# 7Segment-Display-RS232.net
KiCad netlist of a schematic drawn in EAGLE
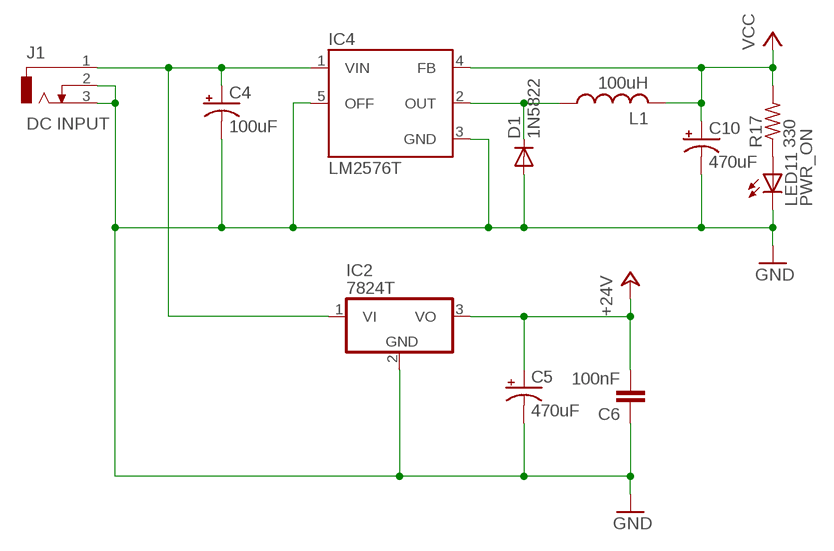
[diagram p0: schematic, sheet 1, part 1 of 2]
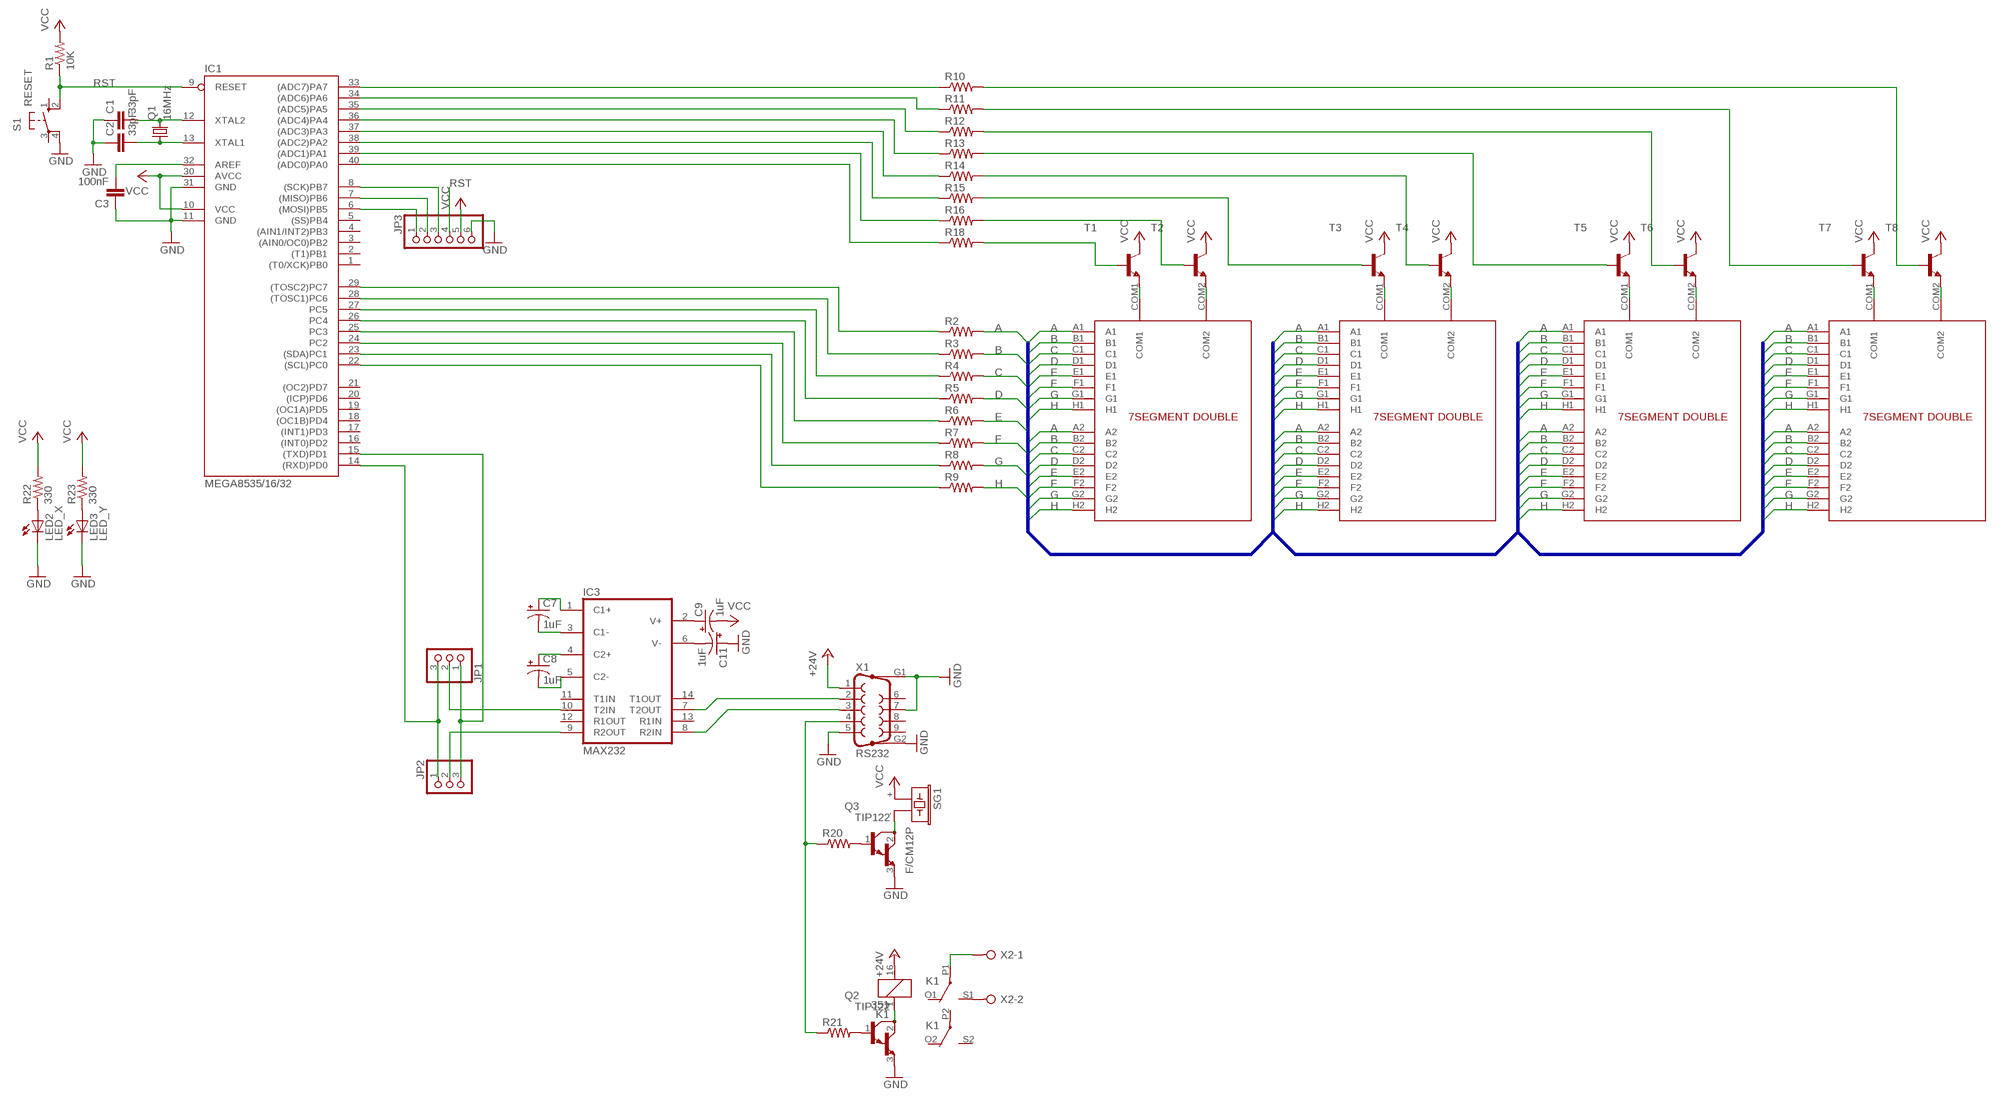
[diagram p1: schematic, sheet 1, part 2 of 2]

(export (version "E")
  (design (tool "Eeschema 10.0.6"))
  (components
    (comp (ref "C1")
      (value "33pF")
      (footprint "eagle-import:C025-024X044")
      (libsource (lib "eagle-import") (part "C-EU025-024X044"))
    )
    (comp (ref "C2")
      (value "33pF")
      (footprint "eagle-import:C025-024X044")
      (libsource (lib "eagle-import") (part "C-EU025-024X044"))
    )
    (comp (ref "C3")
      (value "100nF")
      (footprint "eagle-import:C025-024X044")
      (libsource (lib "eagle-import") (part "C-EU025-024X044"))
    )
    (comp (ref "C4")
      (value "100uF")
      (footprint "eagle-import:E2,5-6")
      (libsource (lib "eagle-import") (part "CPOL-USE2.5-6"))
    )
    (comp (ref "C5")
      (value "470uF")
      (footprint "eagle-import:E3,5-8")
      (libsource (lib "eagle-import") (part "CPOL-USE3.5-8"))
    )
    (comp (ref "C6")
      (value "100nF")
      (footprint "eagle-import:C025-024X044")
      (libsource (lib "eagle-import") (part "C-EU025-024X044"))
    )
    (comp (ref "C7")
      (value "1uF")
      (footprint "eagle-import:E2-4")
      (libsource (lib "eagle-import") (part "CPOL-USE2-4"))
    )
    (comp (ref "C8")
      (value "1uF")
      (footprint "eagle-import:E2-4")
      (libsource (lib "eagle-import") (part "CPOL-USE2-4"))
    )
    (comp (ref "C9")
      (value "1uF")
      (footprint "eagle-import:E2-4")
      (libsource (lib "eagle-import") (part "CPOL-USE2-4"))
    )
    (comp (ref "C10")
      (value "470uF")
      (footprint "eagle-import:E3,5-8")
      (libsource (lib "eagle-import") (part "CPOL-USE3.5-8"))
    )
    (comp (ref "C11")
      (value "1uF")
      (footprint "eagle-import:E2-4")
      (libsource (lib "eagle-import") (part "CPOL-USE2-4"))
    )
    (comp (ref "D1")
      (value "1N5822")
      (footprint "eagle-import:DO201-15")
      (libsource (lib "eagle-import") (part "1N5400"))
    )
    (comp (ref "IC1")
      (value "MEGA8535/16/32")
      (footprint "eagle-import:DIL40")
      (fields (field (name "MPN") "ATMEGA8535-16PU"))
      (libsource (lib "eagle-import") (part "MEGA8535-P"))
    )
    (comp (ref "IC2")
      (value "7824T")
      (footprint "eagle-import:TO220H")
      (libsource (lib "eagle-import") (part "78T24"))
    )
    (comp (ref "IC3")
      (value "MAX232")
      (footprint "eagle-import:DIL16")
      (fields (field (name "MF") "MAXIM") (field (name "MPN") "MAX232ACPE+"))
      (libsource (lib "eagle-import") (part "MAX232"))
    )
    (comp (ref "IC4")
      (value "LM2576T")
      (footprint "eagle-import:TO220-5")
      (libsource (lib "eagle-import") (part "LM2576T"))
    )
    (comp (ref "J1")
      (value "DC INPUT")
      (footprint "eagle-import:DCJ0202")
      (libsource (lib "eagle-import") (part "DCJ0202"))
    )
    (comp (ref "JP1")
      (value "PINHD-1X3")
      (footprint "eagle-import:1X03")
      (libsource (lib "eagle-import") (part "PINHD-1X3"))
    )
    (comp (ref "JP2")
      (value "PINHD-1X3")
      (footprint "eagle-import:1X03")
      (libsource (lib "eagle-import") (part "PINHD-1X3"))
    )
    (comp (ref "JP3")
      (value "PINHD-1X6")
      (footprint "eagle-import:1X06")
      (libsource (lib "eagle-import") (part "PINHD-1X6"))
    )
    (comp (ref "K1")
      (value "351")
      (footprint "eagle-import:351")
      (libsource (lib "eagle-import") (part "351"))
    )
    (comp (ref "L1")
      (value "100uH")
      (footprint "eagle-import:TJ3-U2")
      (libsource (lib "eagle-import") (part "L-USTJ3-U2"))
    )
    (comp (ref "LED2")
      (value "LED_X")
      (footprint "eagle-import:LED3MM")
      (libsource (lib "eagle-import") (part "LED3MM"))
    )
    (comp (ref "LED3")
      (value "LED_Y")
      (footprint "eagle-import:LED3MM")
      (libsource (lib "eagle-import") (part "LED3MM"))
    )
    (comp (ref "LED11")
      (value "PWR_ON")
      (footprint "eagle-import:LED3MM")
      (libsource (lib "eagle-import") (part "LED3MM"))
    )
    (comp (ref "Q1")
      (value "16MHz")
      (footprint "eagle-import:HC49_S")
      (libsource (lib "eagle-import") (part "CRYSTALHC49S"))
    )
    (comp (ref "Q2")
      (value "TIP122")
      (footprint "eagle-import:TO220")
      (libsource (lib "eagle-import") (part "TIP122"))
    )
    (comp (ref "Q3")
      (value "TIP122")
      (footprint "eagle-import:TO220")
      (libsource (lib "eagle-import") (part "TIP122"))
    )
    (comp (ref "R1")
      (value "10K")
      (footprint "eagle-import:0207_10")
      (libsource (lib "eagle-import") (part "R-US_0207/10"))
    )
    (comp (ref "R2")
      (value "R-US_0207/2V")
      (footprint "eagle-import:0207_2V")
      (libsource (lib "eagle-import") (part "R-US_0207/2V"))
    )
    (comp (ref "R3")
      (value "R-US_0207/2V")
      (footprint "eagle-import:0207_2V")
      (libsource (lib "eagle-import") (part "R-US_0207/2V"))
    )
    (comp (ref "R4")
      (value "R-US_0207/2V")
      (footprint "eagle-import:0207_2V")
      (libsource (lib "eagle-import") (part "R-US_0207/2V"))
    )
    (comp (ref "R5")
      (value "R-US_0207/2V")
      (footprint "eagle-import:0207_2V")
      (libsource (lib "eagle-import") (part "R-US_0207/2V"))
    )
    (comp (ref "R6")
      (value "R-US_0207/2V")
      (footprint "eagle-import:0207_2V")
      (libsource (lib "eagle-import") (part "R-US_0207/2V"))
    )
    (comp (ref "R7")
      (value "R-US_0207/2V")
      (footprint "eagle-import:0207_2V")
      (libsource (lib "eagle-import") (part "R-US_0207/2V"))
    )
    (comp (ref "R8")
      (value "R-US_0207/2V")
      (footprint "eagle-import:0207_2V")
      (libsource (lib "eagle-import") (part "R-US_0207/2V"))
    )
    (comp (ref "R9")
      (value "R-US_0207/2V")
      (footprint "eagle-import:0207_2V")
      (libsource (lib "eagle-import") (part "R-US_0207/2V"))
    )
    (comp (ref "R10")
      (value "R-US_0207/2V")
      (footprint "eagle-import:0207_2V")
      (libsource (lib "eagle-import") (part "R-US_0207/2V"))
    )
    (comp (ref "R11")
      (value "R-US_0207/2V")
      (footprint "eagle-import:0207_2V")
      (libsource (lib "eagle-import") (part "R-US_0207/2V"))
    )
    (comp (ref "R12")
      (value "R-US_0207/2V")
      (footprint "eagle-import:0207_2V")
      (libsource (lib "eagle-import") (part "R-US_0207/2V"))
    )
    (comp (ref "R13")
      (value "R-US_0207/2V")
      (footprint "eagle-import:0207_2V")
      (libsource (lib "eagle-import") (part "R-US_0207/2V"))
    )
    (comp (ref "R14")
      (value "R-US_0207/2V")
      (footprint "eagle-import:0207_2V")
      (libsource (lib "eagle-import") (part "R-US_0207/2V"))
    )
    (comp (ref "R15")
      (value "R-US_0207/2V")
      (footprint "eagle-import:0207_2V")
      (libsource (lib "eagle-import") (part "R-US_0207/2V"))
    )
    (comp (ref "R16")
      (value "R-US_0207/2V")
      (footprint "eagle-import:0207_2V")
      (libsource (lib "eagle-import") (part "R-US_0207/2V"))
    )
    (comp (ref "R17")
      (value "330")
      (footprint "eagle-import:0207_2V")
      (libsource (lib "eagle-import") (part "R-US_0207/2V"))
    )
    (comp (ref "R18")
      (value "R-US_0207/2V")
      (footprint "eagle-import:0207_2V")
      (libsource (lib "eagle-import") (part "R-US_0207/2V"))
    )
    (comp (ref "R20")
      (value "R-US_0207/2V")
      (footprint "eagle-import:0207_2V")
      (libsource (lib "eagle-import") (part "R-US_0207/2V"))
    )
    (comp (ref "R21")
      (value "R-US_0207/2V")
      (footprint "eagle-import:0207_2V")
      (libsource (lib "eagle-import") (part "R-US_0207/2V"))
    )
    (comp (ref "R22")
      (value "330")
      (footprint "eagle-import:0207_2V")
      (libsource (lib "eagle-import") (part "R-US_0207/2V"))
    )
    (comp (ref "R23")
      (value "330")
      (footprint "eagle-import:0207_2V")
      (libsource (lib "eagle-import") (part "R-US_0207/2V"))
    )
    (comp (ref "S1")
      (value "RESET")
      (footprint "eagle-import:B3F-10XX")
      (fields (field (name "MPN") "B3F-1000"))
      (libsource (lib "eagle-import") (part "10-XX"))
    )
    (comp (ref "SG1")
      (value "F/CM12P")
      (footprint "eagle-import:F_CM12P")
      (libsource (lib "eagle-import") (part "F/CM12P"))
    )
    (comp (ref "T1")
      (value "2N2222-NPN-TO92-EBC")
      (footprint "eagle-import:TO92-EBC")
      (libsource (lib "eagle-import") (part "-NPN-TO92-EBC2N2222"))
    )
    (comp (ref "T2")
      (value "2N2222-NPN-TO92-EBC")
      (footprint "eagle-import:TO92-EBC")
      (libsource (lib "eagle-import") (part "-NPN-TO92-EBC2N2222"))
    )
    (comp (ref "T3")
      (value "2N2222-NPN-TO92-EBC")
      (footprint "eagle-import:TO92-EBC")
      (libsource (lib "eagle-import") (part "-NPN-TO92-EBC2N2222"))
    )
    (comp (ref "T4")
      (value "2N2222-NPN-TO92-EBC")
      (footprint "eagle-import:TO92-EBC")
      (libsource (lib "eagle-import") (part "-NPN-TO92-EBC2N2222"))
    )
    (comp (ref "T5")
      (value "2N2222-NPN-TO92-EBC")
      (footprint "eagle-import:TO92-EBC")
      (libsource (lib "eagle-import") (part "-NPN-TO92-EBC2N2222"))
    )
    (comp (ref "T6")
      (value "2N2222-NPN-TO92-EBC")
      (footprint "eagle-import:TO92-EBC")
      (libsource (lib "eagle-import") (part "-NPN-TO92-EBC2N2222"))
    )
    (comp (ref "T7")
      (value "2N2222-NPN-TO92-EBC")
      (footprint "eagle-import:TO92-EBC")
      (libsource (lib "eagle-import") (part "-NPN-TO92-EBC2N2222"))
    )
    (comp (ref "T8")
      (value "2N2222-NPN-TO92-EBC")
      (footprint "eagle-import:TO92-EBC")
      (libsource (lib "eagle-import") (part "-NPN-TO92-EBC2N2222"))
    )
    (comp (ref "U$1")
      (value "7SEGMENT_DOUBLE")
      (footprint "eagle-import:7SEGMENT_DOUBLE")
      (libsource (lib "eagle-import") (part "7SEGMENT_DOUBLE"))
    )
    (comp (ref "U$2")
      (value "7SEGMENT_DOUBLE")
      (footprint "eagle-import:7SEGMENT_DOUBLE")
      (libsource (lib "eagle-import") (part "7SEGMENT_DOUBLE"))
    )
    (comp (ref "U$3")
      (value "7SEGMENT_DOUBLE")
      (footprint "eagle-import:7SEGMENT_DOUBLE")
      (libsource (lib "eagle-import") (part "7SEGMENT_DOUBLE"))
    )
    (comp (ref "U$4")
      (value "7SEGMENT_DOUBLE")
      (footprint "eagle-import:7SEGMENT_DOUBLE")
      (libsource (lib "eagle-import") (part "7SEGMENT_DOUBLE"))
    )
    (comp (ref "X1")
      (value "RS232")
      (footprint "eagle-import:F09HP")
      (libsource (lib "eagle-import") (part "F09HP"))
    )
    (comp (ref "X2")
      (value "W237-02P")
      (footprint "eagle-import:W237-132")
      (libsource (lib "eagle-import") (part "W237-02P"))
    )
  )
  (nets
    (net (code "1") (name "+24V") (class "Default")
      (node (ref "C5") (pin "+") (pinfunction "+_+") (pintype "passive"))
      (node (ref "C6") (pin "2") (pinfunction "2_2") (pintype "passive"))
      (node (ref "IC2") (pin "3") (pinfunction "VO_3") (pintype "passive"))
      (node (ref "K1") (pin "16") (pinfunction "2_16") (pintype "passive"))
      (node (ref "X1") (pin "1") (pinfunction "1_1") (pintype "passive"))
    )
    (net (code "2") (name "/A") (class "Default")
      (node (ref "R2") (pin "2") (pinfunction "2_2") (pintype "passive"))
      (node (ref "U$1") (pin "A1") (pinfunction "A1_A1") (pintype "bidirectional"))
      (node (ref "U$1") (pin "A2") (pinfunction "A2_A2") (pintype "bidirectional"))
      (node (ref "U$2") (pin "A1") (pinfunction "A1_A1") (pintype "bidirectional"))
      (node (ref "U$2") (pin "A2") (pinfunction "A2_A2") (pintype "bidirectional"))
      (node (ref "U$3") (pin "A1") (pinfunction "A1_A1") (pintype "bidirectional"))
      (node (ref "U$3") (pin "A2") (pinfunction "A2_A2") (pintype "bidirectional"))
      (node (ref "U$4") (pin "A1") (pinfunction "A1_A1") (pintype "bidirectional"))
      (node (ref "U$4") (pin "A2") (pinfunction "A2_A2") (pintype "bidirectional"))
    )
    (net (code "3") (name "/B") (class "Default")
      (node (ref "R3") (pin "2") (pinfunction "2_2") (pintype "passive"))
      (node (ref "U$1") (pin "B1") (pinfunction "B1_B1") (pintype "bidirectional"))
      (node (ref "U$1") (pin "B2") (pinfunction "B2_B2") (pintype "bidirectional"))
      (node (ref "U$2") (pin "B1") (pinfunction "B1_B1") (pintype "bidirectional"))
      (node (ref "U$2") (pin "B2") (pinfunction "B2_B2") (pintype "bidirectional"))
      (node (ref "U$3") (pin "B1") (pinfunction "B1_B1") (pintype "bidirectional"))
      (node (ref "U$3") (pin "B2") (pinfunction "B2_B2") (pintype "bidirectional"))
      (node (ref "U$4") (pin "B1") (pinfunction "B1_B1") (pintype "bidirectional"))
      (node (ref "U$4") (pin "B2") (pinfunction "B2_B2") (pintype "bidirectional"))
    )
    (net (code "4") (name "/C") (class "Default")
      (node (ref "R4") (pin "2") (pinfunction "2_2") (pintype "passive"))
      (node (ref "U$1") (pin "C1") (pinfunction "C1_C1") (pintype "bidirectional"))
      (node (ref "U$1") (pin "C2") (pinfunction "C2_C2") (pintype "bidirectional"))
      (node (ref "U$2") (pin "C1") (pinfunction "C1_C1") (pintype "bidirectional"))
      (node (ref "U$2") (pin "C2") (pinfunction "C2_C2") (pintype "bidirectional"))
      (node (ref "U$3") (pin "C1") (pinfunction "C1_C1") (pintype "bidirectional"))
      (node (ref "U$3") (pin "C2") (pinfunction "C2_C2") (pintype "bidirectional"))
      (node (ref "U$4") (pin "C1") (pinfunction "C1_C1") (pintype "bidirectional"))
      (node (ref "U$4") (pin "C2") (pinfunction "C2_C2") (pintype "bidirectional"))
    )
    (net (code "5") (name "/D") (class "Default")
      (node (ref "R5") (pin "2") (pinfunction "2_2") (pintype "passive"))
      (node (ref "U$1") (pin "D1") (pinfunction "D1_D1") (pintype "bidirectional"))
      (node (ref "U$1") (pin "D2") (pinfunction "D2_D2") (pintype "bidirectional"))
      (node (ref "U$2") (pin "D1") (pinfunction "D1_D1") (pintype "bidirectional"))
      (node (ref "U$2") (pin "D2") (pinfunction "D2_D2") (pintype "bidirectional"))
      (node (ref "U$3") (pin "D1") (pinfunction "D1_D1") (pintype "bidirectional"))
      (node (ref "U$3") (pin "D2") (pinfunction "D2_D2") (pintype "bidirectional"))
      (node (ref "U$4") (pin "D1") (pinfunction "D1_D1") (pintype "bidirectional"))
      (node (ref "U$4") (pin "D2") (pinfunction "D2_D2") (pintype "bidirectional"))
    )
    (net (code "6") (name "/E") (class "Default")
      (node (ref "R6") (pin "2") (pinfunction "2_2") (pintype "passive"))
      (node (ref "U$1") (pin "E1") (pinfunction "E1_E1") (pintype "bidirectional"))
      (node (ref "U$1") (pin "E2") (pinfunction "E2_E2") (pintype "bidirectional"))
      (node (ref "U$2") (pin "E1") (pinfunction "E1_E1") (pintype "bidirectional"))
      (node (ref "U$2") (pin "E2") (pinfunction "E2_E2") (pintype "bidirectional"))
      (node (ref "U$3") (pin "E1") (pinfunction "E1_E1") (pintype "bidirectional"))
      (node (ref "U$3") (pin "E2") (pinfunction "E2_E2") (pintype "bidirectional"))
      (node (ref "U$4") (pin "E1") (pinfunction "E1_E1") (pintype "bidirectional"))
      (node (ref "U$4") (pin "E2") (pinfunction "E2_E2") (pintype "bidirectional"))
    )
    (net (code "7") (name "/F") (class "Default")
      (node (ref "R7") (pin "2") (pinfunction "2_2") (pintype "passive"))
      (node (ref "U$1") (pin "F1") (pinfunction "F1_F1") (pintype "bidirectional"))
      (node (ref "U$1") (pin "F2") (pinfunction "F2_F2") (pintype "bidirectional"))
      (node (ref "U$2") (pin "F1") (pinfunction "F1_F1") (pintype "bidirectional"))
      (node (ref "U$2") (pin "F2") (pinfunction "F2_F2") (pintype "bidirectional"))
      (node (ref "U$3") (pin "F1") (pinfunction "F1_F1") (pintype "bidirectional"))
      (node (ref "U$3") (pin "F2") (pinfunction "F2_F2") (pintype "bidirectional"))
      (node (ref "U$4") (pin "F1") (pinfunction "F1_F1") (pintype "bidirectional"))
      (node (ref "U$4") (pin "F2") (pinfunction "F2_F2") (pintype "bidirectional"))
    )
    (net (code "8") (name "/G") (class "Default")
      (node (ref "R8") (pin "2") (pinfunction "2_2") (pintype "passive"))
      (node (ref "U$1") (pin "G1") (pinfunction "G1_G1") (pintype "bidirectional"))
      (node (ref "U$1") (pin "G2") (pinfunction "G2_G2") (pintype "bidirectional"))
      (node (ref "U$2") (pin "G1") (pinfunction "G1_G1") (pintype "bidirectional"))
      (node (ref "U$2") (pin "G2") (pinfunction "G2_G2") (pintype "bidirectional"))
      (node (ref "U$3") (pin "G1") (pinfunction "G1_G1") (pintype "bidirectional"))
      (node (ref "U$3") (pin "G2") (pinfunction "G2_G2") (pintype "bidirectional"))
      (node (ref "U$4") (pin "G1") (pinfunction "G1_G1") (pintype "bidirectional"))
      (node (ref "U$4") (pin "G2") (pinfunction "G2_G2") (pintype "bidirectional"))
    )
    (net (code "9") (name "/H") (class "Default")
      (node (ref "R9") (pin "2") (pinfunction "2_2") (pintype "passive"))
      (node (ref "U$1") (pin "H1") (pinfunction "H1_H1") (pintype "bidirectional"))
      (node (ref "U$1") (pin "H2") (pinfunction "H2_H2") (pintype "bidirectional"))
      (node (ref "U$2") (pin "H1") (pinfunction "H1_H1") (pintype "bidirectional"))
      (node (ref "U$2") (pin "H2") (pinfunction "H2_H2") (pintype "bidirectional"))
      (node (ref "U$3") (pin "H1") (pinfunction "H1_H1") (pintype "bidirectional"))
      (node (ref "U$3") (pin "H2") (pinfunction "H2_H2") (pintype "bidirectional"))
      (node (ref "U$4") (pin "H1") (pinfunction "H1_H1") (pintype "bidirectional"))
      (node (ref "U$4") (pin "H2") (pinfunction "H2_H2") (pintype "bidirectional"))
    )
    (net (code "10") (name "/RST") (class "Default")
      (node (ref "IC1") (pin "9") (pinfunction "RESET_9") (pintype "input"))
      (node (ref "JP3") (pin "4") (pinfunction "4_4") (pintype "passive"))
      (node (ref "R1") (pin "1") (pinfunction "1_1") (pintype "passive"))
      (node (ref "S1") (pin "2") (pinfunction "S1_2") (pintype "passive"))
    )
    (net (code "11") (name "GND") (class "Default")
      (node (ref "C1") (pin "1") (pinfunction "1_1") (pintype "passive"))
      (node (ref "C10") (pin "-") (pinfunction "-_-") (pintype "passive"))
      (node (ref "C11") (pin "+") (pinfunction "+_+") (pintype "passive"))
      (node (ref "C2") (pin "1") (pinfunction "1_1") (pintype "passive"))
      (node (ref "C3") (pin "1") (pinfunction "1_1") (pintype "passive"))
      (node (ref "C4") (pin "-") (pinfunction "-_-") (pintype "passive"))
      (node (ref "C5") (pin "-") (pinfunction "-_-") (pintype "passive"))
      (node (ref "C6") (pin "1") (pinfunction "1_1") (pintype "passive"))
      (node (ref "D1") (pin "A") (pinfunction "A_A") (pintype "passive"))
      (node (ref "IC1") (pin "11") (pinfunction "GND_11") (pintype "power_in"))
      (node (ref "IC1") (pin "31") (pinfunction "GND_31") (pintype "power_in"))
      (node (ref "IC2") (pin "2") (pinfunction "GND_2") (pintype "passive"))
      (node (ref "IC4") (pin "3") (pinfunction "GND_3") (pintype "power_in"))
      (node (ref "IC4") (pin "5") (pinfunction "OFF_5") (pintype "input"))
      (node (ref "J1") (pin "2") (pinfunction "2_2") (pintype "passive"))
      (node (ref "J1") (pin "3") (pinfunction "3_3") (pintype "passive"))
      (node (ref "JP3") (pin "6") (pinfunction "6_6") (pintype "passive"))
      (node (ref "LED11") (pin "K") (pinfunction "C_K") (pintype "passive"))
      (node (ref "LED2") (pin "K") (pinfunction "C_K") (pintype "passive"))
      (node (ref "LED3") (pin "K") (pinfunction "C_K") (pintype "passive"))
      (node (ref "Q2") (pin "3") (pinfunction "E_3") (pintype "passive"))
      (node (ref "Q3") (pin "3") (pinfunction "E_3") (pintype "passive"))
      (node (ref "S1") (pin "4") (pinfunction "P1_4") (pintype "passive"))
      (node (ref "X1") (pin "5") (pinfunction "5_5") (pintype "passive"))
      (node (ref "X1") (pin "7") (pinfunction "7_7") (pintype "passive"))
      (node (ref "X1") (pin "G1") (pinfunction "G1_G1") (pintype "passive"))
      (node (ref "X1") (pin "G2") (pinfunction "G2_G2") (pintype "passive"))
    )
    (net (code "12") (name "Net-(IC1-(ADC0)PA0)") (class "Default")
      (node (ref "IC1") (pin "40") (pinfunction "(ADC0)PA0_40") (pintype "bidirectional"))
      (node (ref "R18") (pin "1") (pinfunction "1_1") (pintype "passive"))
    )
    (net (code "13") (name "Net-(IC1-(ADC1)PA1)") (class "Default")
      (node (ref "IC1") (pin "39") (pinfunction "(ADC1)PA1_39") (pintype "bidirectional"))
      (node (ref "R16") (pin "1") (pinfunction "1_1") (pintype "passive"))
    )
    (net (code "14") (name "Net-(IC1-(ADC2)PA2)") (class "Default")
      (node (ref "IC1") (pin "38") (pinfunction "(ADC2)PA2_38") (pintype "bidirectional"))
      (node (ref "R15") (pin "1") (pinfunction "1_1") (pintype "passive"))
    )
    (net (code "15") (name "Net-(IC1-(ADC3)PA3)") (class "Default")
      (node (ref "IC1") (pin "37") (pinfunction "(ADC3)PA3_37") (pintype "bidirectional"))
      (node (ref "R14") (pin "1") (pinfunction "1_1") (pintype "passive"))
    )
    (net (code "16") (name "Net-(IC1-(ADC4)PA4)") (class "Default")
      (node (ref "IC1") (pin "36") (pinfunction "(ADC4)PA4_36") (pintype "bidirectional"))
      (node (ref "R13") (pin "1") (pinfunction "1_1") (pintype "passive"))
    )
    (net (code "17") (name "Net-(IC1-(ADC5)PA5)") (class "Default")
      (node (ref "IC1") (pin "35") (pinfunction "(ADC5)PA5_35") (pintype "bidirectional"))
      (node (ref "R12") (pin "1") (pinfunction "1_1") (pintype "passive"))
    )
    (net (code "18") (name "Net-(IC1-(ADC6)PA6)") (class "Default")
      (node (ref "IC1") (pin "34") (pinfunction "(ADC6)PA6_34") (pintype "bidirectional"))
      (node (ref "R11") (pin "1") (pinfunction "1_1") (pintype "passive"))
    )
    (net (code "19") (name "Net-(IC1-(ADC7)PA7)") (class "Default")
      (node (ref "IC1") (pin "33") (pinfunction "(ADC7)PA7_33") (pintype "bidirectional"))
      (node (ref "R10") (pin "1") (pinfunction "1_1") (pintype "passive"))
    )
    (net (code "20") (name "Net-(IC1-(MISO)PB6)") (class "Default")
      (node (ref "IC1") (pin "7") (pinfunction "(MISO)PB6_7") (pintype "bidirectional"))
      (node (ref "JP3") (pin "2") (pinfunction "2_2") (pintype "passive"))
    )
    (net (code "21") (name "Net-(IC1-(MOSI)PB5)") (class "Default")
      (node (ref "IC1") (pin "6") (pinfunction "(MOSI)PB5_6") (pintype "bidirectional"))
      (node (ref "JP3") (pin "1") (pinfunction "1_1") (pintype "passive"))
    )
    (net (code "22") (name "Net-(IC1-(RXD)PD0)") (class "Default")
      (node (ref "IC1") (pin "14") (pinfunction "(RXD)PD0_14") (pintype "bidirectional"))
      (node (ref "JP1") (pin "3") (pinfunction "3_3") (pintype "passive"))
      (node (ref "JP2") (pin "1") (pinfunction "1_1") (pintype "passive"))
    )
    (net (code "23") (name "Net-(IC1-(SCK)PB7)") (class "Default")
      (node (ref "IC1") (pin "8") (pinfunction "(SCK)PB7_8") (pintype "bidirectional"))
      (node (ref "JP3") (pin "3") (pinfunction "3_3") (pintype "passive"))
    )
    (net (code "24") (name "Net-(IC1-(SCL)PC0)") (class "Default")
      (node (ref "IC1") (pin "22") (pinfunction "(SCL)PC0_22") (pintype "bidirectional"))
      (node (ref "R9") (pin "1") (pinfunction "1_1") (pintype "passive"))
    )
    (net (code "25") (name "Net-(IC1-(SDA)PC1)") (class "Default")
      (node (ref "IC1") (pin "23") (pinfunction "(SDA)PC1_23") (pintype "bidirectional"))
      (node (ref "R8") (pin "1") (pinfunction "1_1") (pintype "passive"))
    )
    (net (code "26") (name "Net-(IC1-(TOSC1)PC6)") (class "Default")
      (node (ref "IC1") (pin "28") (pinfunction "(TOSC1)PC6_28") (pintype "bidirectional"))
      (node (ref "R3") (pin "1") (pinfunction "1_1") (pintype "passive"))
    )
    (net (code "27") (name "Net-(IC1-(TOSC2)PC7)") (class "Default")
      (node (ref "IC1") (pin "29") (pinfunction "(TOSC2)PC7_29") (pintype "bidirectional"))
      (node (ref "R2") (pin "1") (pinfunction "1_1") (pintype "passive"))
    )
    (net (code "28") (name "Net-(IC1-(TXD)PD1)") (class "Default")
      (node (ref "IC1") (pin "15") (pinfunction "(TXD)PD1_15") (pintype "bidirectional"))
      (node (ref "JP1") (pin "1") (pinfunction "1_1") (pintype "passive"))
      (node (ref "JP2") (pin "3") (pinfunction "3_3") (pintype "passive"))
    )
    (net (code "29") (name "Net-(IC1-AREF)") (class "Default")
      (node (ref "C3") (pin "2") (pinfunction "2_2") (pintype "passive"))
      (node (ref "IC1") (pin "32") (pinfunction "AREF_32") (pintype "passive"))
    )
    (net (code "30") (name "Net-(IC1-PC2)") (class "Default")
      (node (ref "IC1") (pin "24") (pinfunction "PC2_24") (pintype "bidirectional"))
      (node (ref "R7") (pin "1") (pinfunction "1_1") (pintype "passive"))
    )
    (net (code "31") (name "Net-(IC1-PC3)") (class "Default")
      (node (ref "IC1") (pin "25") (pinfunction "PC3_25") (pintype "bidirectional"))
      (node (ref "R6") (pin "1") (pinfunction "1_1") (pintype "passive"))
    )
    (net (code "32") (name "Net-(IC1-PC4)") (class "Default")
      (node (ref "IC1") (pin "26") (pinfunction "PC4_26") (pintype "bidirectional"))
      (node (ref "R5") (pin "1") (pinfunction "1_1") (pintype "passive"))
    )
    (net (code "33") (name "Net-(IC1-PC5)") (class "Default")
      (node (ref "IC1") (pin "27") (pinfunction "PC5_27") (pintype "bidirectional"))
      (node (ref "R4") (pin "1") (pinfunction "1_1") (pintype "passive"))
    )
    (net (code "34") (name "Net-(IC1-XTAL1)") (class "Default")
      (node (ref "C2") (pin "2") (pinfunction "2_2") (pintype "passive"))
      (node (ref "IC1") (pin "13") (pinfunction "XTAL1_13") (pintype "bidirectional"))
      (node (ref "Q1") (pin "1") (pinfunction "1_1") (pintype "passive"))
    )
    (net (code "35") (name "Net-(IC1-XTAL2)") (class "Default")
      (node (ref "C1") (pin "2") (pinfunction "2_2") (pintype "passive"))
      (node (ref "IC1") (pin "12") (pinfunction "XTAL2_12") (pintype "bidirectional"))
      (node (ref "Q1") (pin "2") (pinfunction "2_2") (pintype "passive"))
    )
    (net (code "36") (name "Net-(IC2-VI)") (class "Default")
      (node (ref "C4") (pin "+") (pinfunction "+_+") (pintype "passive"))
      (node (ref "IC2") (pin "1") (pinfunction "VI_1") (pintype "input"))
      (node (ref "IC4") (pin "1") (pinfunction "VIN_1") (pintype "power_in"))
      (node (ref "J1") (pin "1") (pinfunction "1_1") (pintype "passive"))
    )
    (net (code "37") (name "Net-(IC3A-C1+)") (class "Default")
      (node (ref "C7") (pin "+") (pinfunction "+_+") (pintype "passive"))
      (node (ref "IC3") (pin "1") (pinfunction "C1+_1") (pintype "bidirectional"))
    )
    (net (code "38") (name "Net-(IC3A-C1-)") (class "Default")
      (node (ref "C7") (pin "-") (pinfunction "-_-") (pintype "passive"))
      (node (ref "IC3") (pin "3") (pinfunction "C1-_3") (pintype "bidirectional"))
    )
    (net (code "39") (name "Net-(IC3A-C2+)") (class "Default")
      (node (ref "C8") (pin "+") (pinfunction "+_+") (pintype "passive"))
      (node (ref "IC3") (pin "4") (pinfunction "C2+_4") (pintype "bidirectional"))
    )
    (net (code "40") (name "Net-(IC3A-C2-)") (class "Default")
      (node (ref "C8") (pin "-") (pinfunction "-_-") (pintype "passive"))
      (node (ref "IC3") (pin "5") (pinfunction "C2-_5") (pintype "bidirectional"))
    )
    (net (code "41") (name "Net-(IC3A-R2IN)") (class "Default")
      (node (ref "IC3") (pin "8") (pinfunction "R2IN_8") (pintype "input"))
      (node (ref "X1") (pin "3") (pinfunction "3_3") (pintype "passive"))
    )
    (net (code "42") (name "Net-(IC3A-R2OUT)") (class "Default")
      (node (ref "IC3") (pin "9") (pinfunction "R2OUT_9") (pintype "output"))
      (node (ref "JP2") (pin "2") (pinfunction "2_2") (pintype "passive"))
    )
    (net (code "43") (name "Net-(IC3A-T2IN)") (class "Default")
      (node (ref "IC3") (pin "10") (pinfunction "T2IN_10") (pintype "input"))
      (node (ref "JP1") (pin "2") (pinfunction "2_2") (pintype "passive"))
    )
    (net (code "44") (name "Net-(IC3A-T2OUT)") (class "Default")
      (node (ref "IC3") (pin "7") (pinfunction "T2OUT_7") (pintype "output"))
      (node (ref "X1") (pin "2") (pinfunction "2_2") (pintype "passive"))
    )
    (net (code "45") (name "Net-(IC3A-V+)") (class "Default")
      (node (ref "C9") (pin "+") (pinfunction "+_+") (pintype "passive"))
      (node (ref "IC3") (pin "2") (pinfunction "V+_2") (pintype "bidirectional"))
    )
    (net (code "46") (name "Net-(IC3A-V-)") (class "Default")
      (node (ref "C11") (pin "-") (pinfunction "-_-") (pintype "passive"))
      (node (ref "IC3") (pin "6") (pinfunction "V-_6") (pintype "bidirectional"))
    )
    (net (code "47") (name "Net-(IC4-OUT)") (class "Default")
      (node (ref "D1") (pin "C") (pinfunction "C_C") (pintype "passive"))
      (node (ref "IC4") (pin "2") (pinfunction "OUT_2") (pintype "output"))
      (node (ref "L1") (pin "1") (pinfunction "1_1") (pintype "passive"))
    )
    (net (code "48") (name "Net-(K1B-P)") (class "Default")
      (node (ref "K1") (pin "P1") (pinfunction "P_P1") (pintype "passive"))
      (node (ref "X2") (pin "1") (pinfunction "KL_1") (pintype "passive"))
    )
    (net (code "49") (name "Net-(K1B-S)") (class "Default")
      (node (ref "K1") (pin "S1") (pinfunction "S_S1") (pintype "passive"))
      (node (ref "X2") (pin "2") (pinfunction "KL_2") (pintype "passive"))
    )
    (net (code "50") (name "Net-(LED2-PadA)") (class "Default")
      (node (ref "LED2") (pin "A") (pinfunction "A_A") (pintype "passive"))
      (node (ref "R22") (pin "1") (pinfunction "1_1") (pintype "passive"))
    )
    (net (code "51") (name "Net-(LED3-PadA)") (class "Default")
      (node (ref "LED3") (pin "A") (pinfunction "A_A") (pintype "passive"))
      (node (ref "R23") (pin "1") (pinfunction "1_1") (pintype "passive"))
    )
    (net (code "52") (name "Net-(LED11-PadA)") (class "Default")
      (node (ref "LED11") (pin "A") (pinfunction "A_A") (pintype "passive"))
      (node (ref "R17") (pin "1") (pinfunction "1_1") (pintype "passive"))
    )
    (net (code "53") (name "Net-(Q2-B)") (class "Default")
      (node (ref "Q2") (pin "1") (pinfunction "B_1") (pintype "passive"))
      (node (ref "R21") (pin "2") (pinfunction "2_2") (pintype "passive"))
    )
    (net (code "54") (name "Net-(Q2-C)") (class "Default")
      (node (ref "K1") (pin "1") (pinfunction "1_1") (pintype "passive"))
      (node (ref "Q2") (pin "2") (pinfunction "C_2") (pintype "passive"))
    )
    (net (code "55") (name "Net-(Q3-B)") (class "Default")
      (node (ref "Q3") (pin "1") (pinfunction "B_1") (pintype "passive"))
      (node (ref "R20") (pin "2") (pinfunction "2_2") (pintype "passive"))
    )
    (net (code "56") (name "Net-(Q3-C)") (class "Default")
      (node (ref "Q3") (pin "2") (pinfunction "C_2") (pintype "passive"))
      (node (ref "SG1") (pin "-") (pinfunction "2_-") (pintype "passive"))
    )
    (net (code "57") (name "Net-(R10-Pad2)") (class "Default")
      (node (ref "R10") (pin "2") (pinfunction "2_2") (pintype "passive"))
      (node (ref "T8") (pin "B") (pinfunction "B_B") (pintype "passive"))
    )
    (net (code "58") (name "Net-(R11-Pad2)") (class "Default")
      (node (ref "R11") (pin "2") (pinfunction "2_2") (pintype "passive"))
      (node (ref "T7") (pin "B") (pinfunction "B_B") (pintype "passive"))
    )
    (net (code "59") (name "Net-(R12-Pad2)") (class "Default")
      (node (ref "R12") (pin "2") (pinfunction "2_2") (pintype "passive"))
      (node (ref "T6") (pin "B") (pinfunction "B_B") (pintype "passive"))
    )
    (net (code "60") (name "Net-(R13-Pad2)") (class "Default")
      (node (ref "R13") (pin "2") (pinfunction "2_2") (pintype "passive"))
      (node (ref "T5") (pin "B") (pinfunction "B_B") (pintype "passive"))
    )
    (net (code "61") (name "Net-(R14-Pad2)") (class "Default")
      (node (ref "R14") (pin "2") (pinfunction "2_2") (pintype "passive"))
      (node (ref "T4") (pin "B") (pinfunction "B_B") (pintype "passive"))
    )
    (net (code "62") (name "Net-(R15-Pad2)") (class "Default")
      (node (ref "R15") (pin "2") (pinfunction "2_2") (pintype "passive"))
      (node (ref "T3") (pin "B") (pinfunction "B_B") (pintype "passive"))
    )
    (net (code "63") (name "Net-(R16-Pad2)") (class "Default")
      (node (ref "R16") (pin "2") (pinfunction "2_2") (pintype "passive"))
      (node (ref "T2") (pin "B") (pinfunction "B_B") (pintype "passive"))
    )
    (net (code "64") (name "Net-(R18-Pad2)") (class "Default")
      (node (ref "R18") (pin "2") (pinfunction "2_2") (pintype "passive"))
      (node (ref "T1") (pin "B") (pinfunction "B_B") (pintype "passive"))
    )
    (net (code "65") (name "Net-(R20-Pad1)") (class "Default")
      (node (ref "R20") (pin "1") (pinfunction "1_1") (pintype "passive"))
      (node (ref "R21") (pin "1") (pinfunction "1_1") (pintype "passive"))
      (node (ref "X1") (pin "4") (pinfunction "4_4") (pintype "passive"))
    )
    (net (code "66") (name "Net-(T1-PadE)") (class "Default")
      (node (ref "T1") (pin "E") (pinfunction "E_E") (pintype "passive"))
      (node (ref "U$1") (pin "COM1") (pinfunction "COM1_COM1") (pintype "bidirectional"))
    )
    (net (code "67") (name "Net-(T2-PadE)") (class "Default")
      (node (ref "T2") (pin "E") (pinfunction "E_E") (pintype "passive"))
      (node (ref "U$1") (pin "COM2") (pinfunction "COM2_COM2") (pintype "bidirectional"))
    )
    (net (code "68") (name "Net-(T3-PadE)") (class "Default")
      (node (ref "T3") (pin "E") (pinfunction "E_E") (pintype "passive"))
      (node (ref "U$2") (pin "COM1") (pinfunction "COM1_COM1") (pintype "bidirectional"))
    )
    (net (code "69") (name "Net-(T4-PadE)") (class "Default")
      (node (ref "T4") (pin "E") (pinfunction "E_E") (pintype "passive"))
      (node (ref "U$2") (pin "COM2") (pinfunction "COM2_COM2") (pintype "bidirectional"))
    )
    (net (code "70") (name "Net-(T5-PadE)") (class "Default")
      (node (ref "T5") (pin "E") (pinfunction "E_E") (pintype "passive"))
      (node (ref "U$3") (pin "COM1") (pinfunction "COM1_COM1") (pintype "bidirectional"))
    )
    (net (code "71") (name "Net-(T6-PadE)") (class "Default")
      (node (ref "T6") (pin "E") (pinfunction "E_E") (pintype "passive"))
      (node (ref "U$3") (pin "COM2") (pinfunction "COM2_COM2") (pintype "bidirectional"))
    )
    (net (code "72") (name "Net-(T7-PadE)") (class "Default")
      (node (ref "T7") (pin "E") (pinfunction "E_E") (pintype "passive"))
      (node (ref "U$4") (pin "COM1") (pinfunction "COM1_COM1") (pintype "bidirectional"))
    )
    (net (code "73") (name "Net-(T8-PadE)") (class "Default")
      (node (ref "T8") (pin "E") (pinfunction "E_E") (pintype "passive"))
      (node (ref "U$4") (pin "COM2") (pinfunction "COM2_COM2") (pintype "bidirectional"))
    )
    (net (code "74") (name "VCC") (class "Default")
      (node (ref "C10") (pin "+") (pinfunction "+_+") (pintype "passive"))
      (node (ref "C9") (pin "-") (pinfunction "-_-") (pintype "passive"))
      (node (ref "IC1") (pin "10") (pinfunction "VCC_10") (pintype "power_in"))
      (node (ref "IC1") (pin "30") (pinfunction "AVCC_30") (pintype "power_in"))
      (node (ref "IC4") (pin "4") (pinfunction "FB_4") (pintype "input"))
      (node (ref "JP3") (pin "5") (pinfunction "5_5") (pintype "passive"))
      (node (ref "L1") (pin "2") (pinfunction "2_2") (pintype "passive"))
      (node (ref "R1") (pin "2") (pinfunction "2_2") (pintype "passive"))
      (node (ref "R17") (pin "2") (pinfunction "2_2") (pintype "passive"))
      (node (ref "R22") (pin "2") (pinfunction "2_2") (pintype "passive"))
      (node (ref "R23") (pin "2") (pinfunction "2_2") (pintype "passive"))
      (node (ref "SG1") (pin "+") (pinfunction "1_+") (pintype "passive"))
      (node (ref "T1") (pin "C") (pinfunction "C_C") (pintype "passive"))
      (node (ref "T2") (pin "C") (pinfunction "C_C") (pintype "passive"))
      (node (ref "T3") (pin "C") (pinfunction "C_C") (pintype "passive"))
      (node (ref "T4") (pin "C") (pinfunction "C_C") (pintype "passive"))
      (node (ref "T5") (pin "C") (pinfunction "C_C") (pintype "passive"))
      (node (ref "T6") (pin "C") (pinfunction "C_C") (pintype "passive"))
      (node (ref "T7") (pin "C") (pinfunction "C_C") (pintype "passive"))
      (node (ref "T8") (pin "C") (pinfunction "C_C") (pintype "passive"))
    )
    (net (code "75") (name "unconnected-(IC1-(AIN0{slash}OC0)PB2-Pad3)") (class "Default")
      (node (ref "IC1") (pin "3") (pinfunction "(AIN0/OC0)PB2_3") (pintype "bidirectional"))
    )
    (net (code "76") (name "unconnected-(IC1-(AIN1{slash}INT2)PB3-Pad4)") (class "Default")
      (node (ref "IC1") (pin "4") (pinfunction "(AIN1/INT2)PB3_4") (pintype "bidirectional"))
    )
    (net (code "77") (name "unconnected-(IC1-(ICP)PD6-Pad20)") (class "Default")
      (node (ref "IC1") (pin "20") (pinfunction "(ICP)PD6_20") (pintype "bidirectional"))
    )
    (net (code "78") (name "unconnected-(IC1-(INT0)PD2-Pad16)") (class "Default")
      (node (ref "IC1") (pin "16") (pinfunction "(INT0)PD2_16") (pintype "bidirectional"))
    )
    (net (code "79") (name "unconnected-(IC1-(INT1)PD3-Pad17)") (class "Default")
      (node (ref "IC1") (pin "17") (pinfunction "(INT1)PD3_17") (pintype "bidirectional"))
    )
    (net (code "80") (name "unconnected-(IC1-(OC1A)PD5-Pad19)") (class "Default")
      (node (ref "IC1") (pin "19") (pinfunction "(OC1A)PD5_19") (pintype "bidirectional"))
    )
    (net (code "81") (name "unconnected-(IC1-(OC1B)PD4-Pad18)") (class "Default")
      (node (ref "IC1") (pin "18") (pinfunction "(OC1B)PD4_18") (pintype "bidirectional"))
    )
    (net (code "82") (name "unconnected-(IC1-(OC2)PD7-Pad21)") (class "Default")
      (node (ref "IC1") (pin "21") (pinfunction "(OC2)PD7_21") (pintype "bidirectional"))
    )
    (net (code "83") (name "unconnected-(IC1-(SS)PB4-Pad5)") (class "Default")
      (node (ref "IC1") (pin "5") (pinfunction "(SS)PB4_5") (pintype "bidirectional"))
    )
    (net (code "84") (name "unconnected-(IC1-(T0{slash}XCK)PB0-Pad1)") (class "Default")
      (node (ref "IC1") (pin "1") (pinfunction "(T0/XCK)PB0_1") (pintype "bidirectional"))
    )
    (net (code "85") (name "unconnected-(IC1-(T1)PB1-Pad2)") (class "Default")
      (node (ref "IC1") (pin "2") (pinfunction "(T1)PB1_2") (pintype "bidirectional"))
    )
    (net (code "86") (name "unconnected-(IC3A-R1IN-Pad13)") (class "Default")
      (node (ref "IC3") (pin "13") (pinfunction "R1IN_13") (pintype "input"))
    )
    (net (code "87") (name "unconnected-(IC3A-R1OUT-Pad12)") (class "Default")
      (node (ref "IC3") (pin "12") (pinfunction "R1OUT_12") (pintype "output"))
    )
    (net (code "88") (name "unconnected-(IC3A-T1IN-Pad11)") (class "Default")
      (node (ref "IC3") (pin "11") (pinfunction "T1IN_11") (pintype "input"))
    )
    (net (code "89") (name "unconnected-(IC3A-T1OUT-Pad14)") (class "Default")
      (node (ref "IC3") (pin "14") (pinfunction "T1OUT_14") (pintype "output"))
    )
    (net (code "90") (name "unconnected-(K1B-O-PadO1)") (class "Default")
      (node (ref "K1") (pin "O1") (pinfunction "O_O1") (pintype "passive"))
    )
    (net (code "91") (name "unconnected-(K1C-O-PadO2)") (class "Default")
      (node (ref "K1") (pin "O2") (pinfunction "O_O2") (pintype "passive"))
    )
    (net (code "92") (name "unconnected-(K1C-P-PadP2)") (class "Default")
      (node (ref "K1") (pin "P2") (pinfunction "P_P2") (pintype "passive"))
    )
    (net (code "93") (name "unconnected-(K1C-S-PadS2)") (class "Default")
      (node (ref "K1") (pin "S2") (pinfunction "S_S2") (pintype "passive"))
    )
    (net (code "94") (name "unconnected-(S1-P-Pad3)") (class "Default")
      (node (ref "S1") (pin "3") (pinfunction "P_3") (pintype "passive"))
    )
    (net (code "95") (name "unconnected-(S1-S-Pad1)") (class "Default")
      (node (ref "S1") (pin "1") (pinfunction "S_1") (pintype "passive"))
    )
    (net (code "96") (name "unconnected-(X1-Pad6)") (class "Default")
      (node (ref "X1") (pin "6") (pinfunction "6_6") (pintype "passive"))
    )
    (net (code "97") (name "unconnected-(X1-Pad8)") (class "Default")
      (node (ref "X1") (pin "8") (pinfunction "8_8") (pintype "passive"))
    )
    (net (code "98") (name "unconnected-(X1-Pad9)") (class "Default")
      (node (ref "X1") (pin "9") (pinfunction "9_9") (pintype "passive"))
    )
  )
)
